# CRM100.net
KiCad netlist of a schematic drawn in Altium Designer
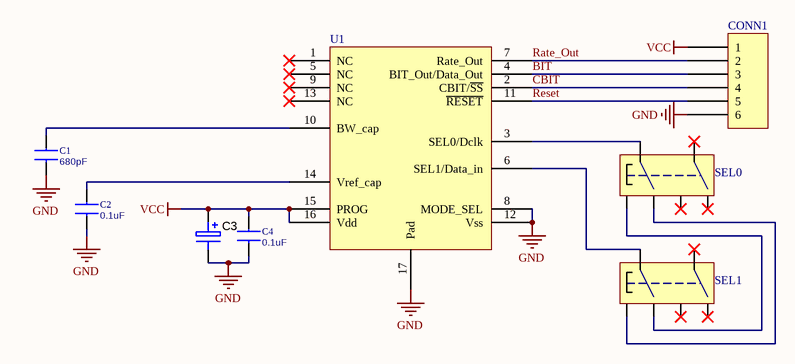
[diagram p0: CRM100.SchDoc]

(export (version "E")
  (design (tool "Eeschema 10.0.6"))
  (components
    (comp (ref "C1")
      (value "680pF")
      (footprint "C_0805")
      (description "Capacitor")
      (libsource (lib "AX_Altium_v2.3") (part "C0805"))
    )
    (comp (ref "C2")
      (value "0.1uF")
      (footprint "C_0805")
      (description "Capacitor")
      (libsource (lib "AX_Altium_v2.3") (part "C0805"))
    )
    (comp (ref "C3")
      (value "~")
      (footprint "General_Lib:CAPMP3216X180N")
      (description "Capacitor SMD Tantalum 4.7uF 10% 16V 3216-18")
      (fields (field (name "TOLERANCE") "±10%"))
      (libsource (lib "General_Lib") (part "CAP_TANT_TYPE_A"))
    )
    (comp (ref "C4")
      (value "0.1uF")
      (footprint "C_0805")
      (description "Capacitor")
      (libsource (lib "AX_Altium_v2.3") (part "C0805"))
    )
    (comp (ref "CONN1")
      (value "6_pin_plate_conn")
      (footprint "6_pin_plate_conn")
      (libsource (lib "AD_lib") (part "6_pin_plate_conn"))
    )
    (comp (ref "SEL0")
      (value "IS-1390 switch")
      (footprint "IS1390")
      (libsource (lib "AD_lib") (part "IS-1390"))
    )
    (comp (ref "SEL1")
      (value "IS-1390 switch")
      (footprint "IS1390")
      (libsource (lib "AD_lib") (part "IS-1390"))
    )
    (comp (ref "U1")
      (value "CRM100 gyroscope")
      (footprint "CRM100")
      (libsource (lib "AD_lib") (part "CRM100"))
    )
  )
  (nets
    (net (code "1") (name "/BIT") (class "Default")
      (node (ref "CONN1") (pin "3") (pinfunction "3_3") (pintype "passive"))
      (node (ref "U1") (pin "4") (pinfunction "BIT_Out/Data_Out_4") (pintype "passive"))
    )
    (net (code "2") (name "/CBIT") (class "Default")
      (node (ref "CONN1") (pin "4") (pinfunction "4_4") (pintype "passive"))
      (node (ref "U1") (pin "2") (pinfunction "CBIT/~{SS}_2") (pintype "passive"))
    )
    (net (code "3") (name "/Rate_Out") (class "Default")
      (node (ref "CONN1") (pin "2") (pinfunction "2_2") (pintype "passive"))
      (node (ref "U1") (pin "7") (pinfunction "Rate_Out_7") (pintype "passive"))
    )
    (net (code "4") (name "/Reset") (class "Default")
      (node (ref "CONN1") (pin "5") (pinfunction "5_5") (pintype "passive"))
      (node (ref "U1") (pin "11") (pinfunction "~{RESET}_11") (pintype "passive"))
    )
    (net (code "5") (name "GND") (class "Default")
      (node (ref "C1") (pin "1") (pintype "passive"))
      (node (ref "C2") (pin "1") (pintype "passive"))
      (node (ref "C3") (pin "2") (pintype "passive"))
      (node (ref "C4") (pin "1") (pintype "passive"))
      (node (ref "CONN1") (pin "6") (pinfunction "6_6") (pintype "passive"))
      (node (ref "U1") (pin "12") (pinfunction "Vss_12") (pintype "passive"))
      (node (ref "U1") (pin "17") (pinfunction "Pad_17") (pintype "passive"))
      (node (ref "U1") (pin "8") (pinfunction "MODE_SEL_8") (pintype "passive"))
    )
    (net (code "6") (name "Net-(SEL0-Pad4)") (class "Default")
      (node (ref "SEL0") (pin "4") (pinfunction "4_4") (pintype "passive"))
      (node (ref "SEL1") (pin "6") (pinfunction "6_6") (pintype "passive"))
    )
    (net (code "7") (name "Net-(SEL0-Pad6)") (class "Default")
      (node (ref "SEL0") (pin "6") (pinfunction "6_6") (pintype "passive"))
      (node (ref "SEL1") (pin "4") (pinfunction "4_4") (pintype "passive"))
    )
    (net (code "8") (name "Net-(U1-BW_cap)") (class "Default")
      (node (ref "C1") (pin "2") (pintype "passive"))
      (node (ref "U1") (pin "10") (pinfunction "BW_cap_10") (pintype "passive"))
    )
    (net (code "9") (name "Net-(U1-SEL0{slash}Dclk)") (class "Default")
      (node (ref "SEL0") (pin "5") (pinfunction "5_5") (pintype "passive"))
      (node (ref "U1") (pin "3") (pinfunction "SEL0/Dclk_3") (pintype "passive"))
    )
    (net (code "10") (name "Net-(U1-SEL1{slash}Data_in)") (class "Default")
      (node (ref "SEL1") (pin "5") (pinfunction "5_5") (pintype "passive"))
      (node (ref "U1") (pin "6") (pinfunction "SEL1/Data_in_6") (pintype "passive"))
    )
    (net (code "11") (name "Net-(U1-Vref_cap)") (class "Default")
      (node (ref "C2") (pin "2") (pintype "passive"))
      (node (ref "U1") (pin "14") (pinfunction "Vref_cap_14") (pintype "passive"))
    )
    (net (code "12") (name "VCC") (class "Default")
      (node (ref "C3") (pin "1") (pintype "passive"))
      (node (ref "C4") (pin "2") (pintype "passive"))
      (node (ref "CONN1") (pin "1") (pinfunction "1_1") (pintype "passive"))
      (node (ref "U1") (pin "15") (pinfunction "PROG_15") (pintype "passive"))
      (node (ref "U1") (pin "16") (pinfunction "Vdd_16") (pintype "passive"))
    )
    (net (code "13") (name "unconnected-(SEL0-Pad1)") (class "Default")
      (node (ref "SEL0") (pin "1") (pinfunction "1_1") (pintype "passive+no_connect"))
    )
    (net (code "14") (name "unconnected-(SEL0-Pad2)") (class "Default")
      (node (ref "SEL0") (pin "2") (pinfunction "2_2") (pintype "passive+no_connect"))
    )
    (net (code "15") (name "unconnected-(SEL0-Pad3)") (class "Default")
      (node (ref "SEL0") (pin "3") (pinfunction "3_3") (pintype "passive+no_connect"))
    )
    (net (code "16") (name "unconnected-(SEL1-Pad1)") (class "Default")
      (node (ref "SEL1") (pin "1") (pinfunction "1_1") (pintype "passive+no_connect"))
    )
    (net (code "17") (name "unconnected-(SEL1-Pad2)") (class "Default")
      (node (ref "SEL1") (pin "2") (pinfunction "2_2") (pintype "passive+no_connect"))
    )
    (net (code "18") (name "unconnected-(SEL1-Pad3)") (class "Default")
      (node (ref "SEL1") (pin "3") (pinfunction "3_3") (pintype "passive+no_connect"))
    )
    (net (code "19") (name "unconnected-(U1-NC-Pad1)") (class "Default")
      (node (ref "U1") (pin "1") (pinfunction "NC_1") (pintype "passive+no_connect"))
    )
    (net (code "20") (name "unconnected-(U1-NC-Pad5)") (class "Default")
      (node (ref "U1") (pin "5") (pinfunction "NC_5") (pintype "passive+no_connect"))
    )
    (net (code "21") (name "unconnected-(U1-NC-Pad9)") (class "Default")
      (node (ref "U1") (pin "9") (pinfunction "NC_9") (pintype "passive+no_connect"))
    )
    (net (code "22") (name "unconnected-(U1-NC-Pad13)") (class "Default")
      (node (ref "U1") (pin "13") (pinfunction "NC_13") (pintype "passive+no_connect"))
    )
  )
)
